# CMS015.net
KiCad netlist of a schematic drawn in Altium Designer
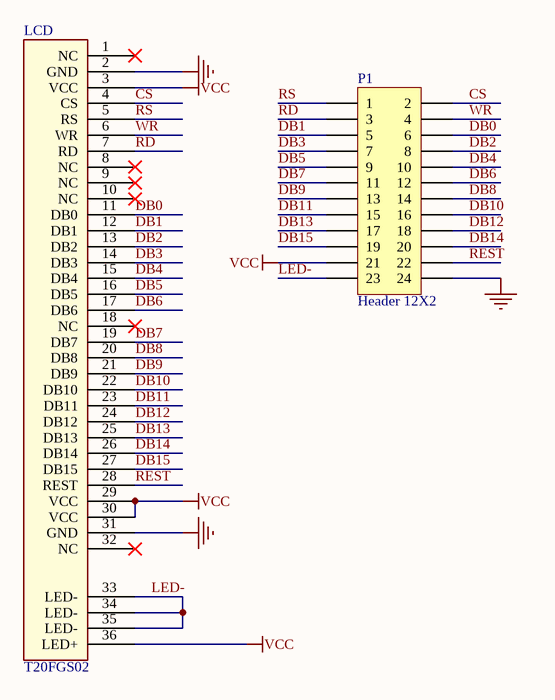
[diagram p0: CMS015.SchDoc]

(export (version "E")
  (design (tool "Eeschema 10.0.6"))
  (components
    (comp (ref "LCD")
      (value "T20FGS02")
      (footprint "LCD_T20FGS02")
      (libsource (lib "Tiky") (part "LCD_T20FGS02"))
    )
    (comp (ref "P1")
      (value "Header 12X2")
      (footprint "HDR2X12")
      (description "Header, 12-Pin, Dual row")
      (fields (field (name "PUBLISHER") "Altium Limited"))
      (libsource (lib "Miscellaneous Connectors") (part "Header 12X2"))
    )
  )
  (nets
    (net (code "1") (name "/CS") (class "Default")
      (node (ref "LCD") (pin "4") (pinfunction "CS_4") (pintype "passive"))
      (node (ref "P1") (pin "2") (pinfunction "2_2") (pintype "passive"))
    )
    (net (code "2") (name "/DB0") (class "Default")
      (node (ref "LCD") (pin "11") (pinfunction "DB0_11") (pintype "passive"))
      (node (ref "P1") (pin "6") (pinfunction "6_6") (pintype "passive"))
    )
    (net (code "3") (name "/DB1") (class "Default")
      (node (ref "LCD") (pin "12") (pinfunction "DB1_12") (pintype "passive"))
      (node (ref "P1") (pin "5") (pinfunction "5_5") (pintype "passive"))
    )
    (net (code "4") (name "/DB2") (class "Default")
      (node (ref "LCD") (pin "13") (pinfunction "DB2_13") (pintype "passive"))
      (node (ref "P1") (pin "8") (pinfunction "8_8") (pintype "passive"))
    )
    (net (code "5") (name "/DB3") (class "Default")
      (node (ref "LCD") (pin "14") (pinfunction "DB3_14") (pintype "passive"))
      (node (ref "P1") (pin "7") (pinfunction "7_7") (pintype "passive"))
    )
    (net (code "6") (name "/DB4") (class "Default")
      (node (ref "LCD") (pin "15") (pinfunction "DB4_15") (pintype "passive"))
      (node (ref "P1") (pin "10") (pinfunction "10_10") (pintype "passive"))
    )
    (net (code "7") (name "/DB5") (class "Default")
      (node (ref "LCD") (pin "16") (pinfunction "DB5_16") (pintype "passive"))
      (node (ref "P1") (pin "9") (pinfunction "9_9") (pintype "passive"))
    )
    (net (code "8") (name "/DB6") (class "Default")
      (node (ref "LCD") (pin "17") (pinfunction "DB6_17") (pintype "passive"))
      (node (ref "P1") (pin "12") (pinfunction "12_12") (pintype "passive"))
    )
    (net (code "9") (name "/DB7") (class "Default")
      (node (ref "LCD") (pin "19") (pinfunction "DB7_19") (pintype "passive"))
      (node (ref "P1") (pin "11") (pinfunction "11_11") (pintype "passive"))
    )
    (net (code "10") (name "/DB8") (class "Default")
      (node (ref "LCD") (pin "20") (pinfunction "DB8_20") (pintype "passive"))
      (node (ref "P1") (pin "14") (pinfunction "14_14") (pintype "passive"))
    )
    (net (code "11") (name "/DB9") (class "Default")
      (node (ref "LCD") (pin "21") (pinfunction "DB9_21") (pintype "passive"))
      (node (ref "P1") (pin "13") (pinfunction "13_13") (pintype "passive"))
    )
    (net (code "12") (name "/DB10") (class "Default")
      (node (ref "LCD") (pin "22") (pinfunction "DB10_22") (pintype "passive"))
      (node (ref "P1") (pin "16") (pinfunction "16_16") (pintype "passive"))
    )
    (net (code "13") (name "/DB11") (class "Default")
      (node (ref "LCD") (pin "23") (pinfunction "DB11_23") (pintype "passive"))
      (node (ref "P1") (pin "15") (pinfunction "15_15") (pintype "passive"))
    )
    (net (code "14") (name "/DB12") (class "Default")
      (node (ref "LCD") (pin "24") (pinfunction "DB12_24") (pintype "passive"))
      (node (ref "P1") (pin "18") (pinfunction "18_18") (pintype "passive"))
    )
    (net (code "15") (name "/DB13") (class "Default")
      (node (ref "LCD") (pin "25") (pinfunction "DB13_25") (pintype "passive"))
      (node (ref "P1") (pin "17") (pinfunction "17_17") (pintype "passive"))
    )
    (net (code "16") (name "/DB14") (class "Default")
      (node (ref "LCD") (pin "26") (pinfunction "DB14_26") (pintype "passive"))
      (node (ref "P1") (pin "20") (pinfunction "20_20") (pintype "passive"))
    )
    (net (code "17") (name "/DB15") (class "Default")
      (node (ref "LCD") (pin "27") (pinfunction "DB15_27") (pintype "passive"))
      (node (ref "P1") (pin "19") (pinfunction "19_19") (pintype "passive"))
    )
    (net (code "18") (name "/LED-") (class "Default")
      (node (ref "LCD") (pin "33") (pinfunction "LED-_33") (pintype "passive"))
      (node (ref "LCD") (pin "34") (pinfunction "LED-_34") (pintype "passive"))
      (node (ref "LCD") (pin "35") (pinfunction "LED-_35") (pintype "passive"))
      (node (ref "P1") (pin "23") (pinfunction "23_23") (pintype "passive"))
    )
    (net (code "19") (name "/RD") (class "Default")
      (node (ref "LCD") (pin "7") (pinfunction "RD_7") (pintype "passive"))
      (node (ref "P1") (pin "3") (pinfunction "3_3") (pintype "passive"))
    )
    (net (code "20") (name "/REST") (class "Default")
      (node (ref "LCD") (pin "28") (pinfunction "REST_28") (pintype "passive"))
      (node (ref "P1") (pin "22") (pinfunction "22_22") (pintype "passive"))
    )
    (net (code "21") (name "/RS") (class "Default")
      (node (ref "LCD") (pin "5") (pinfunction "RS_5") (pintype "passive"))
      (node (ref "P1") (pin "1") (pinfunction "1_1") (pintype "passive"))
    )
    (net (code "22") (name "/WR") (class "Default")
      (node (ref "LCD") (pin "6") (pinfunction "WR_6") (pintype "passive"))
      (node (ref "P1") (pin "4") (pinfunction "4_4") (pintype "passive"))
    )
    (net (code "23") (name "GND") (class "Default")
      (node (ref "LCD") (pin "2") (pinfunction "GND_2") (pintype "passive"))
      (node (ref "LCD") (pin "31") (pinfunction "GND_31") (pintype "passive"))
      (node (ref "P1") (pin "24") (pinfunction "24_24") (pintype "passive"))
    )
    (net (code "24") (name "VCC") (class "Default")
      (node (ref "LCD") (pin "29") (pinfunction "VCC_29") (pintype "passive"))
      (node (ref "LCD") (pin "3") (pinfunction "VCC_3") (pintype "passive"))
      (node (ref "LCD") (pin "30") (pinfunction "VCC_30") (pintype "passive"))
      (node (ref "LCD") (pin "36") (pinfunction "LED+_36") (pintype "passive"))
      (node (ref "P1") (pin "21") (pinfunction "21_21") (pintype "passive"))
    )
    (net (code "25") (name "unconnected-(LCD-NC-Pad1)") (class "Default")
      (node (ref "LCD") (pin "1") (pinfunction "NC_1") (pintype "passive+no_connect"))
    )
    (net (code "26") (name "unconnected-(LCD-NC-Pad8)") (class "Default")
      (node (ref "LCD") (pin "8") (pinfunction "NC_8") (pintype "passive+no_connect"))
    )
    (net (code "27") (name "unconnected-(LCD-NC-Pad9)") (class "Default")
      (node (ref "LCD") (pin "9") (pinfunction "NC_9") (pintype "passive+no_connect"))
    )
    (net (code "28") (name "unconnected-(LCD-NC-Pad10)") (class "Default")
      (node (ref "LCD") (pin "10") (pinfunction "NC_10") (pintype "passive+no_connect"))
    )
    (net (code "29") (name "unconnected-(LCD-NC-Pad18)") (class "Default")
      (node (ref "LCD") (pin "18") (pinfunction "NC_18") (pintype "passive+no_connect"))
    )
    (net (code "30") (name "unconnected-(LCD-NC-Pad32)") (class "Default")
      (node (ref "LCD") (pin "32") (pinfunction "NC_32") (pintype "passive+no_connect"))
    )
  )
)
